# Sheet4.net
KiCad netlist of a schematic drawn in Altium Designer
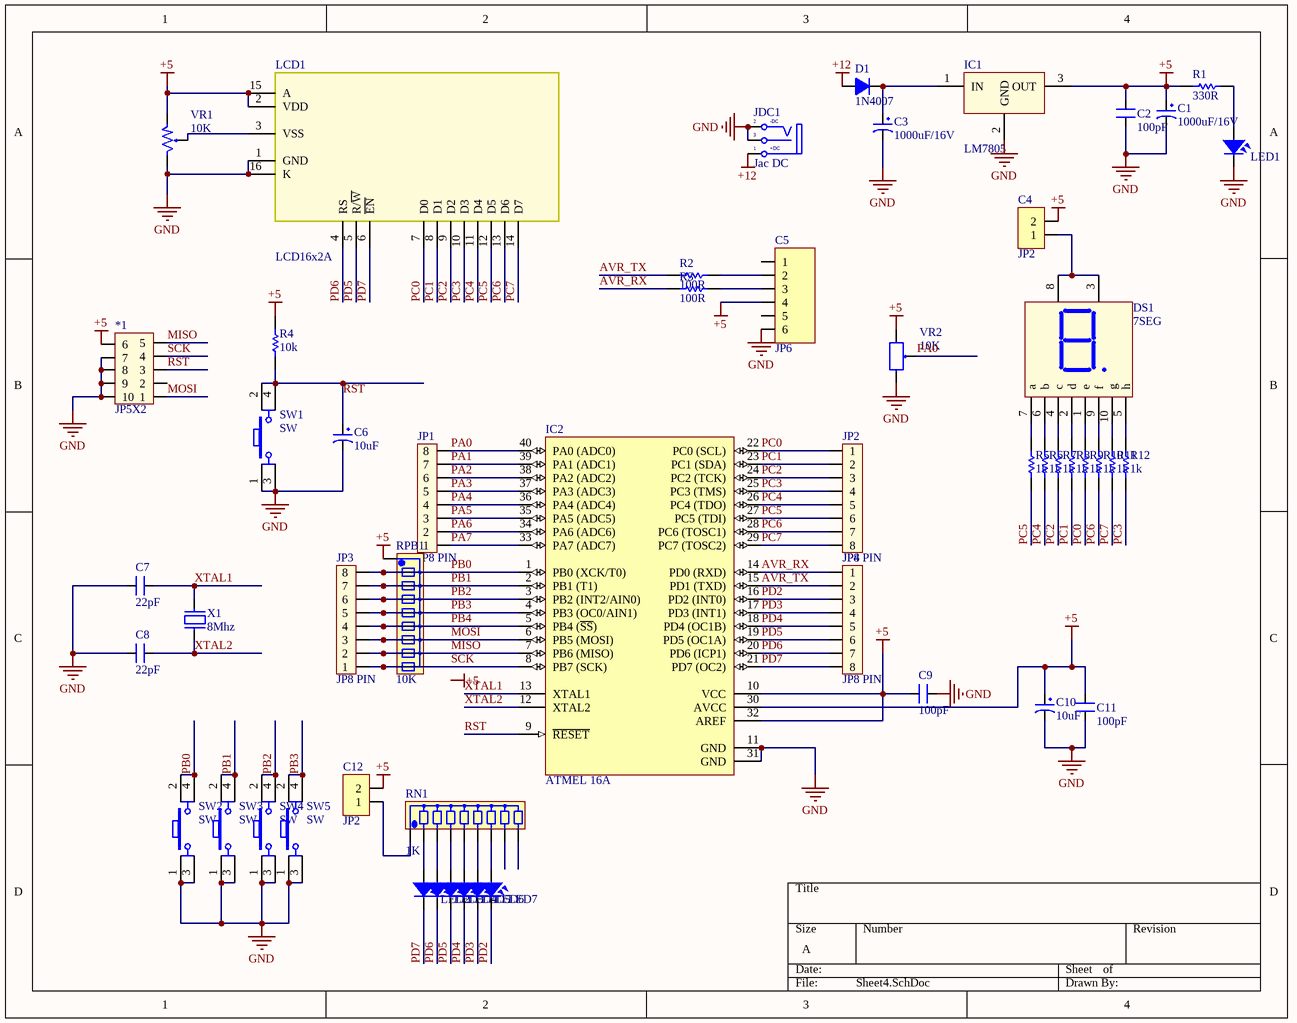
[diagram p0: Sheet4.SchDoc]

(export (version "E")
  (design (tool "Eeschema 10.0.6"))
  (components
    (comp (ref "*1") (value "JP5X2") (footprint "JP5X2") (libsource (lib "syhaunguyen") (part "JP5X2")))
    (comp (ref "C1")
      (value "1000uF/16V")
      (footprint "CP1.5/3.4")
      (description "Cap 1000uF/16V - 220uF/50V")
      (libsource (lib "syhaunguyen") (part "CP4"))
    )
    (comp (ref "C2")
      (value "100pF")
      (footprint "CN1")
      (description "Cap np  1pF - 472pF")
      (libsource (lib "syhaunguyen") (part "CN1"))
    )
    (comp (ref "C3")
      (value "1000uF/16V")
      (footprint "CP1.5/3.4")
      (description "Cap 1000uF/16V - 220uF/50V")
      (libsource (lib "syhaunguyen") (part "CP4"))
    )
    (comp (ref "C4")
      (value "JP2")
      (footprint "JP2-D1T")
      (description "WR-PHD 2.54 mm Angled Socket Header")
      (fields
        (field (name "MANUFACTURER") "Würth Elektronik eiSos GmbH")
        (field (name "PARTNO") "613002143121")
        (field (name "CREATED BY") "Karrer Zheng")
      )
      (libsource (lib "TechMT.VN_Lib_Project v2") (part "JP2"))
    )
    (comp (ref "C5")
      (value "JP6")
      (footprint "JP6-D1T")
      (description "WR-PHD 2.54 mm Angled Socket Header")
      (fields
        (field (name "MANUFACTURER") "Würth Elektronik eiSos GmbH")
        (field (name "PARTNO") "613006143121")
        (field (name "CREATED BY") "Karrer Zheng")
      )
      (libsource (lib "LIBRARY") (part "JP6"))
    )
    (comp (ref "C6")
      (value "10uF")
      (footprint "CP1/2")
      (description "Cap P  0,1uF < 22uF , 16 - 50V")
      (libsource (lib "syhaunguyen") (part "CP1"))
    )
    (comp (ref "C7")
      (value "22pF")
      (footprint "CN1")
      (description "Cap np  1pF - 472pF")
      (libsource (lib "syhaunguyen") (part "CN1"))
    )
    (comp (ref "C8")
      (value "22pF")
      (footprint "CN1")
      (description "Cap np  1pF - 472pF")
      (libsource (lib "syhaunguyen") (part "CN1"))
    )
    (comp (ref "C9")
      (value "100pF")
      (footprint "CN1")
      (description "Cap np  1pF - 472pF")
      (libsource (lib "syhaunguyen") (part "CN1"))
    )
    (comp (ref "C10")
      (value "10uF")
      (footprint "CP1/2")
      (description "Cap P  0,1uF < 22uF , 16 - 50V")
      (libsource (lib "syhaunguyen") (part "CP1"))
    )
    (comp (ref "C11")
      (value "100pF")
      (footprint "CN1")
      (description "Cap np  1pF - 472pF")
      (libsource (lib "syhaunguyen") (part "CN1"))
    )
    (comp (ref "C12")
      (value "JP2")
      (footprint "JP2-D1T")
      (description "WR-PHD 2.54 mm Angled Socket Header")
      (fields
        (field (name "MANUFACTURER") "Würth Elektronik eiSos GmbH")
        (field (name "PARTNO") "613002143121")
        (field (name "CREATED BY") "Karrer Zheng")
      )
      (libsource (lib "TechMT.VN_Lib_Project v2") (part "JP2"))
    )
    (comp (ref "D1")
      (value "1N4007")
      (footprint "D1A")
      (description "Diode 1A")
      (libsource (lib "syhaunguyen") (part "D1A"))
    )
    (comp (ref "DS1")
      (value "7SEG")
      (footprint "LED7SEG-1-0.56")
      (description "14.2 mm General Purpose Blue 7-Segment Display: CC, RH DP, Gray Surface")
      (fields (field (name "PUBLISHER") "Altium Limited"))
      (libsource (lib "TechMT.VN_Lib_Project v2") (part "LED7SEG-1"))
    )
    (comp (ref "IC1")
      (value "LM7805")
      (footprint "QTO-220")
      (description "On ap +, from + 5 to + 24VDC")
      (libsource (lib "syhaunguyen") (part "LM78xx"))
    )
    (comp (ref "IC2")
      (value "ATMEL 16A")
      (footprint "DIP40/W0.6")
      (description "8-Bit AVR Microcontroller with 16K Bytes of In-System Programmable Flash Memory")
      (libsource (lib "LIBRARY") (part "ATmega16A-PU"))
    )
    (comp (ref "JDC1")
      (value "Jac DC")
      (footprint "DC-IN")
      (description "Jac DC input")
      (libsource (lib "syhaunguyen") (part "DCIN"))
    )
    (comp (ref "JP1") (value "JP8 PIN") (footprint "JP8") (libsource (lib "") (part "JP8_1")))
    (comp (ref "JP2") (value "JP8 PIN") (footprint "JP8") (libsource (lib "syhaunguyen") (part "JP8")))
    (comp (ref "JP3") (value "JP8 PIN") (footprint "JP8") (libsource (lib "") (part "JP8_1")))
    (comp (ref "JP4") (value "JP8 PIN") (footprint "JP8") (libsource (lib "syhaunguyen") (part "JP8")))
    (comp (ref "LCD1")
      (value "LCD16x2A")
      (footprint "LCD16X2")
      (description "LCD dipslay 16 char, 2 line")
      (libsource (lib "syhaunguyen") (part "LCD16x2"))
    )
    (comp (ref "LED1")
      (value "LED")
      (footprint "LED-5-RED")
      (description "LED Single colour Green and Red")
      (libsource (lib "syhaunguyen") (part "LED"))
    )
    (comp (ref "LED2")
      (value "LED")
      (footprint "LED-3")
      (description "LED Single colour Green and Red")
      (libsource (lib "syhaunguyen") (part "LED"))
    )
    (comp (ref "LED3")
      (value "LED")
      (footprint "LED-3")
      (description "LED Single colour Green and Red")
      (libsource (lib "syhaunguyen") (part "LED"))
    )
    (comp (ref "LED4")
      (value "LED")
      (footprint "LED-3")
      (description "LED Single colour Green and Red")
      (libsource (lib "syhaunguyen") (part "LED"))
    )
    (comp (ref "LED5")
      (value "LED")
      (footprint "LED-3")
      (description "LED Single colour Green and Red")
      (libsource (lib "syhaunguyen") (part "LED"))
    )
    (comp (ref "LED6")
      (value "LED")
      (footprint "LED-3")
      (description "LED Single colour Green and Red")
      (libsource (lib "syhaunguyen") (part "LED"))
    )
    (comp (ref "LED7")
      (value "LED")
      (footprint "LED-3")
      (description "LED Single colour Green and Red")
      (libsource (lib "syhaunguyen") (part "LED"))
    )
    (comp (ref "R1")
      (value "330R")
      (footprint "R1/4W")
      (description "Resistor")
      (fields
        (field (name "MANUFACTURER") "Generic Components")
        (field (name "Comment") "Res1")
        (field (name "PUBLISHER") "Altium Hobart Technology Centre")
      )
      (libsource (lib "syhaunguyen") (part "Res1_1"))
    )
    (comp (ref "R2")
      (value "100R")
      (footprint "R1/4W")
      (description "Resistor")
      (fields
        (field (name "MANUFACTURER") "Generic Components")
        (field (name "Comment") "Res1")
        (field (name "PUBLISHER") "Altium Hobart Technology Centre")
      )
      (libsource (lib "syhaunguyen") (part "Res1_1"))
    )
    (comp (ref "R3")
      (value "100R")
      (footprint "R1/4W")
      (description "Resistor")
      (fields
        (field (name "MANUFACTURER") "Generic Components")
        (field (name "Comment") "Res1")
        (field (name "PUBLISHER") "Altium Hobart Technology Centre")
      )
      (libsource (lib "syhaunguyen") (part "Res1_1"))
    )
    (comp (ref "R4")
      (value "10k")
      (footprint "R1/4W")
      (description "Resistor")
      (fields
        (field (name "MANUFACTURER") "Generic Components")
        (field (name "Comment") "Res1")
        (field (name "PUBLISHER") "Altium Hobart Technology Centre")
      )
      (libsource (lib "syhaunguyen") (part "Res1_1"))
    )
    (comp (ref "R5")
      (value "1k")
      (footprint "R1/4W")
      (description "Resistor")
      (fields
        (field (name "MANUFACTURER") "Generic Components")
        (field (name "Comment") "Res1")
        (field (name "PUBLISHER") "Altium Hobart Technology Centre")
      )
      (libsource (lib "syhaunguyen") (part "Res1_1"))
    )
    (comp (ref "R6")
      (value "1k")
      (footprint "R1/4W")
      (description "Resistor")
      (fields
        (field (name "MANUFACTURER") "Generic Components")
        (field (name "Comment") "Res1")
        (field (name "PUBLISHER") "Altium Hobart Technology Centre")
      )
      (libsource (lib "syhaunguyen") (part "Res1_1"))
    )
    (comp (ref "R7")
      (value "1k")
      (footprint "R1/4W")
      (description "Resistor")
      (fields
        (field (name "MANUFACTURER") "Generic Components")
        (field (name "Comment") "Res1")
        (field (name "PUBLISHER") "Altium Hobart Technology Centre")
      )
      (libsource (lib "syhaunguyen") (part "Res1_1"))
    )
    (comp (ref "R8")
      (value "1k")
      (footprint "R1/4W")
      (description "Resistor")
      (fields
        (field (name "MANUFACTURER") "Generic Components")
        (field (name "Comment") "Res1")
        (field (name "PUBLISHER") "Altium Hobart Technology Centre")
      )
      (libsource (lib "syhaunguyen") (part "Res1_1"))
    )
    (comp (ref "R9")
      (value "1k")
      (footprint "R1/4W")
      (description "Resistor")
      (fields
        (field (name "MANUFACTURER") "Generic Components")
        (field (name "Comment") "Res1")
        (field (name "PUBLISHER") "Altium Hobart Technology Centre")
      )
      (libsource (lib "syhaunguyen") (part "Res1_1"))
    )
    (comp (ref "R10")
      (value "1k")
      (footprint "R1/4W")
      (description "Resistor")
      (fields
        (field (name "MANUFACTURER") "Generic Components")
        (field (name "Comment") "Res1")
        (field (name "PUBLISHER") "Altium Hobart Technology Centre")
      )
      (libsource (lib "syhaunguyen") (part "Res1_1"))
    )
    (comp (ref "R11")
      (value "1k")
      (footprint "R1/4W")
      (description "Resistor")
      (fields
        (field (name "MANUFACTURER") "Generic Components")
        (field (name "Comment") "Res1")
        (field (name "PUBLISHER") "Altium Hobart Technology Centre")
      )
      (libsource (lib "syhaunguyen") (part "Res1_1"))
    )
    (comp (ref "R12")
      (value "1k")
      (footprint "R1/4W")
      (description "Resistor")
      (fields
        (field (name "MANUFACTURER") "Generic Components")
        (field (name "Comment") "Res1")
        (field (name "PUBLISHER") "Altium Hobart Technology Centre")
      )
      (libsource (lib "syhaunguyen") (part "Res1_1"))
    )
    (comp (ref "RN1")
      (value "1K")
      (footprint "RN8")
      (description "Resistor 8 (Thanh)")
      (libsource (lib "syhaunguyen") (part "RN8"))
    )
    (comp (ref "RPB1")
      (value "10K")
      (footprint "RN8")
      (description "Resistor 8 (Thanh)")
      (libsource (lib "LIBRARY") (part "RN8"))
    )
    (comp (ref "SW1")
      (value "SW")
      (footprint "SW4")
      (description "Switch button 4 pin")
      (libsource (lib "syhaunguyen") (part "SW4"))
    )
    (comp (ref "SW2")
      (value "SW")
      (footprint "SW4")
      (description "Switch button 4 pin")
      (libsource (lib "syhaunguyen") (part "SW4"))
    )
    (comp (ref "SW3")
      (value "SW")
      (footprint "SW4")
      (description "Switch button 4 pin")
      (libsource (lib "syhaunguyen") (part "SW4"))
    )
    (comp (ref "SW4")
      (value "SW")
      (footprint "SW4")
      (description "Switch button 4 pin")
      (libsource (lib "syhaunguyen") (part "SW4"))
    )
    (comp (ref "SW5")
      (value "SW")
      (footprint "SW4")
      (description "Switch button 4 pin")
      (libsource (lib "syhaunguyen") (part "SW4"))
    )
    (comp (ref "VR1")
      (value "10K")
      (footprint "VR")
      (description "Var Resistor")
      (libsource (lib "syhaunguyen") (part "VR1"))
    )
    (comp (ref "VR2")
      (value "10K")
      (footprint "VR1")
      (description "Var Resistor")
      (libsource (lib "syhaunguyen") (part "VR"))
    )
    (comp (ref "X1")
      (value "8Mhz")
      (footprint "XT2")
      (description "Crystal For all Crystal 2pin.")
      (libsource (lib "syhaunguyen") (part "XT2"))
    )
  )
  (nets
    (net (code "1") (name "+5") (class "Default")
      (node (ref "*1") (pin "6") (pinfunction "6_6") (pintype "passive"))
      (node (ref "C1") (pin "1") (pinfunction "1_1") (pintype "passive"))
      (node (ref "C10") (pin "1") (pinfunction "1_1") (pintype "passive"))
      (node (ref "C11") (pin "2") (pinfunction "2_2") (pintype "passive"))
      (node (ref "C12") (pin "2") (pinfunction "2_2") (pintype "passive"))
      (node (ref "C2") (pin "1") (pinfunction "1_1") (pintype "passive"))
      (node (ref "C4") (pin "2") (pinfunction "2_2") (pintype "passive"))
      (node (ref "C5") (pin "4") (pinfunction "4_4") (pintype "passive"))
      (node (ref "C9") (pin "1") (pinfunction "1_1") (pintype "passive"))
      (node (ref "IC1") (pin "3") (pinfunction "OUT_3") (pintype "passive"))
      (node (ref "IC2") (pin "10") (pinfunction "VCC_10") (pintype "power_in"))
      (node (ref "IC2") (pin "30") (pinfunction "AVCC_30") (pintype "power_in"))
      (node (ref "IC2") (pin "32") (pinfunction "AREF_32") (pintype "power_in"))
      (node (ref "LCD1") (pin "15") (pinfunction "A_15") (pintype "passive"))
      (node (ref "LCD1") (pin "2") (pinfunction "VDD_2") (pintype "passive"))
      (node (ref "R1") (pin "2") (pinfunction "2_2") (pintype "passive"))
      (node (ref "R4") (pin "1") (pinfunction "1_1") (pintype "passive"))
      (node (ref "RPB1") (pin "1") (pinfunction "1_1") (pintype "passive"))
      (node (ref "VR1") (pin "1") (pinfunction "1_1") (pintype "passive"))
      (node (ref "VR2") (pin "1") (pinfunction "1_1") (pintype "passive"))
    )
    (net (code "2") (name "+12") (class "Default")
      (node (ref "D1") (pin "1") (pinfunction "A_1") (pintype "passive"))
      (node (ref "JDC1") (pin "1") (pinfunction "T_1") (pintype "passive"))
    )
    (net (code "3") (name "/AVR_RX") (class "Default")
      (node (ref "IC2") (pin "14") (pinfunction "PD0_(RXD)_14") (pintype "bidirectional"))
      (node (ref "JP4") (pin "1") (pinfunction "1_1") (pintype "passive"))
      (node (ref "R3") (pin "2") (pinfunction "2_2") (pintype "passive"))
    )
    (net (code "4") (name "/AVR_TX") (class "Default")
      (node (ref "IC2") (pin "15") (pinfunction "PD1_(TXD)_15") (pintype "bidirectional"))
      (node (ref "JP4") (pin "2") (pinfunction "2_2") (pintype "passive"))
      (node (ref "R2") (pin "2") (pinfunction "2_2") (pintype "passive"))
    )
    (net (code "5") (name "/MISO") (class "Default")
      (node (ref "*1") (pin "5") (pinfunction "5_5") (pintype "passive"))
      (node (ref "IC2") (pin "7") (pinfunction "PB6_(MISO)_7") (pintype "bidirectional"))
      (node (ref "JP3") (pin "2") (pinfunction "2_2") (pintype "passive"))
      (node (ref "RPB1") (pin "8") (pinfunction "8_8") (pintype "passive"))
    )
    (net (code "6") (name "/MOSI") (class "Default")
      (node (ref "*1") (pin "1") (pinfunction "1_1") (pintype "passive"))
      (node (ref "IC2") (pin "6") (pinfunction "PB5_(MOSI)_6") (pintype "bidirectional"))
      (node (ref "JP3") (pin "3") (pinfunction "3_3") (pintype "passive"))
      (node (ref "RPB1") (pin "7") (pinfunction "7_7") (pintype "passive"))
    )
    (net (code "7") (name "/PA0") (class "Default")
      (node (ref "IC2") (pin "40") (pinfunction "PA0_(ADC0)_40") (pintype "bidirectional"))
      (node (ref "JP1") (pin "8") (pinfunction "8_8") (pintype "passive"))
      (node (ref "VR2") (pin "2") (pinfunction "2_2") (pintype "passive"))
    )
    (net (code "8") (name "/PA1") (class "Default")
      (node (ref "IC2") (pin "39") (pinfunction "PA1_(ADC1)_39") (pintype "bidirectional"))
      (node (ref "JP1") (pin "7") (pinfunction "7_7") (pintype "passive"))
    )
    (net (code "9") (name "/PA2") (class "Default")
      (node (ref "IC2") (pin "38") (pinfunction "PA2_(ADC2)_38") (pintype "bidirectional"))
      (node (ref "JP1") (pin "6") (pinfunction "6_6") (pintype "passive"))
    )
    (net (code "10") (name "/PA3") (class "Default")
      (node (ref "IC2") (pin "37") (pinfunction "PA3_(ADC3)_37") (pintype "bidirectional"))
      (node (ref "JP1") (pin "5") (pinfunction "5_5") (pintype "passive"))
    )
    (net (code "11") (name "/PA4") (class "Default")
      (node (ref "IC2") (pin "36") (pinfunction "PA4_(ADC4)_36") (pintype "bidirectional"))
      (node (ref "JP1") (pin "4") (pinfunction "4_4") (pintype "passive"))
    )
    (net (code "12") (name "/PA5") (class "Default")
      (node (ref "IC2") (pin "35") (pinfunction "PA5_(ADC5)_35") (pintype "bidirectional"))
      (node (ref "JP1") (pin "3") (pinfunction "3_3") (pintype "passive"))
    )
    (net (code "13") (name "/PA6") (class "Default")
      (node (ref "IC2") (pin "34") (pinfunction "PA6_(ADC6)_34") (pintype "bidirectional"))
      (node (ref "JP1") (pin "2") (pinfunction "2_2") (pintype "passive"))
    )
    (net (code "14") (name "/PA7") (class "Default")
      (node (ref "IC2") (pin "33") (pinfunction "PA7_(ADC7)_33") (pintype "bidirectional"))
      (node (ref "JP1") (pin "1") (pinfunction "1_1") (pintype "passive"))
    )
    (net (code "15") (name "/PB0") (class "Default")
      (node (ref "IC2") (pin "1") (pinfunction "PB0_(XCK/T0)_1") (pintype "bidirectional"))
      (node (ref "JP3") (pin "8") (pinfunction "8_8") (pintype "passive"))
      (node (ref "RPB1") (pin "2") (pinfunction "2_2") (pintype "passive"))
      (node (ref "SW2") (pin "2") (pintype "passive"))
      (node (ref "SW2") (pin "4") (pintype "passive"))
    )
    (net (code "16") (name "/PB1") (class "Default")
      (node (ref "IC2") (pin "2") (pinfunction "PB1_(T1)_2") (pintype "bidirectional"))
      (node (ref "JP3") (pin "7") (pinfunction "7_7") (pintype "passive"))
      (node (ref "RPB1") (pin "3") (pinfunction "3_3") (pintype "passive"))
      (node (ref "SW3") (pin "2") (pintype "passive"))
      (node (ref "SW3") (pin "4") (pintype "passive"))
    )
    (net (code "17") (name "/PB2") (class "Default")
      (node (ref "IC2") (pin "3") (pinfunction "PB2_(INT2/AIN0)_3") (pintype "bidirectional"))
      (node (ref "JP3") (pin "6") (pinfunction "6_6") (pintype "passive"))
      (node (ref "RPB1") (pin "4") (pinfunction "4_4") (pintype "passive"))
      (node (ref "SW4") (pin "2") (pintype "passive"))
      (node (ref "SW4") (pin "4") (pintype "passive"))
    )
    (net (code "18") (name "/PB3") (class "Default")
      (node (ref "IC2") (pin "4") (pinfunction "PB3_(OC0/AIN1)_4") (pintype "bidirectional"))
      (node (ref "JP3") (pin "5") (pinfunction "5_5") (pintype "passive"))
      (node (ref "RPB1") (pin "5") (pinfunction "5_5") (pintype "passive"))
      (node (ref "SW5") (pin "2") (pintype "passive"))
      (node (ref "SW5") (pin "4") (pintype "passive"))
    )
    (net (code "19") (name "/PB4") (class "Default")
      (node (ref "IC2") (pin "5") (pinfunction "PB4_(~{SS})_5") (pintype "bidirectional"))
      (node (ref "JP3") (pin "4") (pinfunction "4_4") (pintype "passive"))
      (node (ref "RPB1") (pin "6") (pinfunction "6_6") (pintype "passive"))
    )
    (net (code "20") (name "/PC0") (class "Default")
      (node (ref "IC2") (pin "22") (pinfunction "PC0_(SCL)_22") (pintype "bidirectional"))
      (node (ref "JP2") (pin "1") (pinfunction "1_1") (pintype "passive"))
      (node (ref "LCD1") (pin "7") (pinfunction "D0_7") (pintype "passive"))
      (node (ref "R9") (pin "2") (pinfunction "2_2") (pintype "passive"))
    )
    (net (code "21") (name "/PC1") (class "Default")
      (node (ref "IC2") (pin "23") (pinfunction "PC1_(SDA)_23") (pintype "bidirectional"))
      (node (ref "JP2") (pin "2") (pinfunction "2_2") (pintype "passive"))
      (node (ref "LCD1") (pin "8") (pinfunction "D1_8") (pintype "passive"))
      (node (ref "R8") (pin "2") (pinfunction "2_2") (pintype "passive"))
    )
    (net (code "22") (name "/PC2") (class "Default")
      (node (ref "IC2") (pin "24") (pinfunction "PC2_(TCK)_24") (pintype "bidirectional"))
      (node (ref "JP2") (pin "3") (pinfunction "3_3") (pintype "passive"))
      (node (ref "LCD1") (pin "9") (pinfunction "D2_9") (pintype "passive"))
      (node (ref "R7") (pin "2") (pinfunction "2_2") (pintype "passive"))
    )
    (net (code "23") (name "/PC3") (class "Default")
      (node (ref "IC2") (pin "25") (pinfunction "PC3_(TMS)_25") (pintype "bidirectional"))
      (node (ref "JP2") (pin "4") (pinfunction "4_4") (pintype "passive"))
      (node (ref "LCD1") (pin "10") (pinfunction "D3_10") (pintype "passive"))
      (node (ref "R12") (pin "2") (pinfunction "2_2") (pintype "passive"))
    )
    (net (code "24") (name "/PC4") (class "Default")
      (node (ref "IC2") (pin "26") (pinfunction "PC4_(TDO)_26") (pintype "bidirectional"))
      (node (ref "JP2") (pin "5") (pinfunction "5_5") (pintype "passive"))
      (node (ref "LCD1") (pin "11") (pinfunction "D4_11") (pintype "passive"))
      (node (ref "R6") (pin "2") (pinfunction "2_2") (pintype "passive"))
    )
    (net (code "25") (name "/PC5") (class "Default")
      (node (ref "IC2") (pin "27") (pinfunction "PC5_(TDI)_27") (pintype "bidirectional"))
      (node (ref "JP2") (pin "6") (pinfunction "6_6") (pintype "passive"))
      (node (ref "LCD1") (pin "12") (pinfunction "D5_12") (pintype "passive"))
      (node (ref "R5") (pin "2") (pinfunction "2_2") (pintype "passive"))
    )
    (net (code "26") (name "/PC6") (class "Default")
      (node (ref "IC2") (pin "28") (pinfunction "PC6_(TOSC1)_28") (pintype "bidirectional"))
      (node (ref "JP2") (pin "7") (pinfunction "7_7") (pintype "passive"))
      (node (ref "LCD1") (pin "13") (pinfunction "D6_13") (pintype "passive"))
      (node (ref "R10") (pin "2") (pinfunction "2_2") (pintype "passive"))
    )
    (net (code "27") (name "/PC7") (class "Default")
      (node (ref "IC2") (pin "29") (pinfunction "PC7_(TOSC2)_29") (pintype "bidirectional"))
      (node (ref "JP2") (pin "8") (pinfunction "8_8") (pintype "passive"))
      (node (ref "LCD1") (pin "14") (pinfunction "D7_14") (pintype "passive"))
      (node (ref "R11") (pin "2") (pinfunction "2_2") (pintype "passive"))
    )
    (net (code "28") (name "/PD2") (class "Default")
      (node (ref "IC2") (pin "16") (pinfunction "PD2_(INT0)_16") (pintype "bidirectional"))
      (node (ref "JP4") (pin "3") (pinfunction "3_3") (pintype "passive"))
      (node (ref "LED7") (pin "2") (pinfunction "2_2") (pintype "passive"))
    )
    (net (code "29") (name "/PD3") (class "Default")
      (node (ref "IC2") (pin "17") (pinfunction "PD3_(INT1)_17") (pintype "bidirectional"))
      (node (ref "JP4") (pin "4") (pinfunction "4_4") (pintype "passive"))
      (node (ref "LED6") (pin "2") (pinfunction "2_2") (pintype "passive"))
    )
    (net (code "30") (name "/PD4") (class "Default")
      (node (ref "IC2") (pin "18") (pinfunction "PD4_(OC1B)_18") (pintype "bidirectional"))
      (node (ref "JP4") (pin "5") (pinfunction "5_5") (pintype "passive"))
      (node (ref "LED5") (pin "2") (pinfunction "2_2") (pintype "passive"))
    )
    (net (code "31") (name "/PD5") (class "Default")
      (node (ref "IC2") (pin "19") (pinfunction "PD5_(OC1A)_19") (pintype "bidirectional"))
      (node (ref "JP4") (pin "6") (pinfunction "6_6") (pintype "passive"))
      (node (ref "LCD1") (pin "5") (pinfunction "R/~{W}_5") (pintype "passive"))
      (node (ref "LED4") (pin "2") (pinfunction "2_2") (pintype "passive"))
    )
    (net (code "32") (name "/PD6") (class "Default")
      (node (ref "IC2") (pin "20") (pinfunction "PD6_(ICP1)_20") (pintype "bidirectional"))
      (node (ref "JP4") (pin "7") (pinfunction "7_7") (pintype "passive"))
      (node (ref "LCD1") (pin "4") (pinfunction "RS_4") (pintype "passive"))
      (node (ref "LED3") (pin "2") (pinfunction "2_2") (pintype "passive"))
    )
    (net (code "33") (name "/PD7") (class "Default")
      (node (ref "IC2") (pin "21") (pinfunction "PD7_(OC2)_21") (pintype "bidirectional"))
      (node (ref "JP4") (pin "8") (pinfunction "8_8") (pintype "passive"))
      (node (ref "LCD1") (pin "6") (pinfunction "~{EN}_6") (pintype "passive"))
      (node (ref "LED2") (pin "2") (pinfunction "2_2") (pintype "passive"))
    )
    (net (code "34") (name "/RST") (class "Default")
      (node (ref "*1") (pin "3") (pinfunction "3_3") (pintype "passive"))
      (node (ref "C6") (pin "1") (pinfunction "1_1") (pintype "passive"))
      (node (ref "IC2") (pin "9") (pinfunction "~{RESET}_9") (pintype "input"))
      (node (ref "R4") (pin "2") (pinfunction "2_2") (pintype "passive"))
      (node (ref "SW1") (pin "2") (pintype "passive"))
      (node (ref "SW1") (pin "4") (pintype "passive"))
    )
    (net (code "35") (name "/SCK") (class "Default")
      (node (ref "*1") (pin "4") (pinfunction "4_4") (pintype "passive"))
      (node (ref "IC2") (pin "8") (pinfunction "PB7_(SCK)_8") (pintype "bidirectional"))
      (node (ref "JP3") (pin "1") (pinfunction "1_1") (pintype "passive"))
      (node (ref "RPB1") (pin "9") (pinfunction "9_9") (pintype "passive"))
    )
    (net (code "36") (name "/XTAL1") (class "Default")
      (node (ref "C7") (pin "2") (pinfunction "2_2") (pintype "passive"))
      (node (ref "IC2") (pin "13") (pinfunction "XTAL1_13") (pintype "passive"))
      (node (ref "X1") (pin "2") (pinfunction "2_2") (pintype "passive"))
    )
    (net (code "37") (name "/XTAL2") (class "Default")
      (node (ref "C8") (pin "2") (pinfunction "2_2") (pintype "passive"))
      (node (ref "IC2") (pin "12") (pinfunction "XTAL2_12") (pintype "passive"))
      (node (ref "X1") (pin "1") (pinfunction "1_1") (pintype "passive"))
    )
    (net (code "38") (name "GND") (class "Default")
      (node (ref "*1") (pin "10") (pinfunction "10_10") (pintype "passive"))
      (node (ref "*1") (pin "7") (pinfunction "7_7") (pintype "passive"))
      (node (ref "*1") (pin "8") (pinfunction "8_8") (pintype "passive"))
      (node (ref "*1") (pin "9") (pinfunction "9_9") (pintype "passive"))
      (node (ref "C1") (pin "2") (pinfunction "2_2") (pintype "passive"))
      (node (ref "C10") (pin "2") (pinfunction "2_2") (pintype "passive"))
      (node (ref "C11") (pin "1") (pinfunction "1_1") (pintype "passive"))
      (node (ref "C2") (pin "2") (pinfunction "2_2") (pintype "passive"))
      (node (ref "C3") (pin "2") (pinfunction "2_2") (pintype "passive"))
      (node (ref "C5") (pin "6") (pinfunction "6_6") (pintype "passive"))
      (node (ref "C6") (pin "2") (pinfunction "2_2") (pintype "passive"))
      (node (ref "C7") (pin "1") (pinfunction "1_1") (pintype "passive"))
      (node (ref "C8") (pin "1") (pinfunction "1_1") (pintype "passive"))
      (node (ref "C9") (pin "2") (pinfunction "2_2") (pintype "passive"))
      (node (ref "IC1") (pin "2") (pinfunction "GND_2") (pintype "passive"))
      (node (ref "IC2") (pin "11") (pinfunction "GND_11") (pintype "power_in"))
      (node (ref "IC2") (pin "31") (pinfunction "GND_31") (pintype "power_in"))
      (node (ref "JDC1") (pin "2") (pinfunction "TN_2") (pintype "passive"))
      (node (ref "JDC1") (pin "3") (pinfunction "S_3") (pintype "power_in"))
      (node (ref "LCD1") (pin "1") (pinfunction "GND_1") (pintype "passive"))
      (node (ref "LCD1") (pin "16") (pinfunction "K_16") (pintype "passive"))
      (node (ref "LED1") (pin "2") (pinfunction "2_2") (pintype "passive"))
      (node (ref "SW1") (pin "1") (pintype "passive"))
      (node (ref "SW1") (pin "3") (pintype "passive"))
      (node (ref "SW2") (pin "1") (pintype "passive"))
      (node (ref "SW2") (pin "3") (pintype "passive"))
      (node (ref "SW3") (pin "1") (pintype "passive"))
      (node (ref "SW3") (pin "3") (pintype "passive"))
      (node (ref "SW4") (pin "1") (pintype "passive"))
      (node (ref "SW4") (pin "3") (pintype "passive"))
      (node (ref "SW5") (pin "1") (pintype "passive"))
      (node (ref "SW5") (pin "3") (pintype "passive"))
      (node (ref "VR1") (pin "3") (pinfunction "3_3") (pintype "passive"))
      (node (ref "VR2") (pin "3") (pinfunction "3_3") (pintype "passive"))
    )
    (net (code "39") (name "Net-(C4-Pad1)") (class "Default")
      (node (ref "C4") (pin "1") (pinfunction "1_1") (pintype "passive"))
      (node (ref "DS1") (pin "3") (pinfunction "Vcc_3") (pintype "passive"))
      (node (ref "DS1") (pin "8") (pinfunction "Vcc_8") (pintype "passive"))
    )
    (net (code "40") (name "Net-(C5-Pad2)") (class "Default")
      (node (ref "C5") (pin "2") (pinfunction "2_2") (pintype "passive"))
      (node (ref "R2") (pin "1") (pinfunction "1_1") (pintype "passive"))
    )
    (net (code "41") (name "Net-(C5-Pad3)") (class "Default")
      (node (ref "C5") (pin "3") (pinfunction "3_3") (pintype "passive"))
      (node (ref "R3") (pin "1") (pinfunction "1_1") (pintype "passive"))
    )
    (net (code "42") (name "Net-(C12-Pad1)") (class "Default")
      (node (ref "C12") (pin "1") (pinfunction "1_1") (pintype "passive"))
      (node (ref "RN1") (pin "1") (pinfunction "1_1") (pintype "passive"))
    )
    (net (code "43") (name "Net-(D1-K)") (class "Default")
      (node (ref "C3") (pin "1") (pinfunction "1_1") (pintype "passive"))
      (node (ref "D1") (pin "2") (pinfunction "K_2") (pintype "passive"))
      (node (ref "IC1") (pin "1") (pinfunction "IN_1") (pintype "passive"))
    )
    (net (code "44") (name "Net-(DS1-a)") (class "Default")
      (node (ref "DS1") (pin "7") (pinfunction "a_7") (pintype "passive"))
      (node (ref "R5") (pin "1") (pinfunction "1_1") (pintype "passive"))
    )
    (net (code "45") (name "Net-(DS1-b)") (class "Default")
      (node (ref "DS1") (pin "6") (pinfunction "b_6") (pintype "passive"))
      (node (ref "R6") (pin "1") (pinfunction "1_1") (pintype "passive"))
    )
    (net (code "46") (name "Net-(DS1-c)") (class "Default")
      (node (ref "DS1") (pin "4") (pinfunction "c_4") (pintype "passive"))
      (node (ref "R7") (pin "1") (pinfunction "1_1") (pintype "passive"))
    )
    (net (code "47") (name "Net-(DS1-d)") (class "Default")
      (node (ref "DS1") (pin "2") (pinfunction "d_2") (pintype "passive"))
      (node (ref "R8") (pin "1") (pinfunction "1_1") (pintype "passive"))
    )
    (net (code "48") (name "Net-(DS1-e)") (class "Default")
      (node (ref "DS1") (pin "1") (pinfunction "e_1") (pintype "passive"))
      (node (ref "R9") (pin "1") (pinfunction "1_1") (pintype "passive"))
    )
    (net (code "49") (name "Net-(DS1-f)") (class "Default")
      (node (ref "DS1") (pin "9") (pinfunction "f_9") (pintype "passive"))
      (node (ref "R10") (pin "1") (pinfunction "1_1") (pintype "passive"))
    )
    (net (code "50") (name "Net-(DS1-g)") (class "Default")
      (node (ref "DS1") (pin "10") (pinfunction "g_10") (pintype "passive"))
      (node (ref "R11") (pin "1") (pinfunction "1_1") (pintype "passive"))
    )
    (net (code "51") (name "Net-(DS1-h)") (class "Default")
      (node (ref "DS1") (pin "5") (pinfunction "h_5") (pintype "passive"))
      (node (ref "R12") (pin "1") (pinfunction "1_1") (pintype "passive"))
    )
    (net (code "52") (name "Net-(LCD1-VSS)") (class "Default")
      (node (ref "LCD1") (pin "3") (pinfunction "VSS_3") (pintype "passive"))
      (node (ref "VR1") (pin "2") (pinfunction "2_2") (pintype "passive"))
    )
    (net (code "53") (name "Net-(LED1-Pad1)") (class "Default")
      (node (ref "LED1") (pin "1") (pinfunction "1_1") (pintype "passive"))
      (node (ref "R1") (pin "1") (pinfunction "1_1") (pintype "passive"))
    )
    (net (code "54") (name "Net-(LED2-Pad1)") (class "Default")
      (node (ref "LED2") (pin "1") (pinfunction "1_1") (pintype "passive"))
      (node (ref "RN1") (pin "2") (pinfunction "2_2") (pintype "passive"))
    )
    (net (code "55") (name "Net-(LED3-Pad1)") (class "Default")
      (node (ref "LED3") (pin "1") (pinfunction "1_1") (pintype "passive"))
      (node (ref "RN1") (pin "3") (pinfunction "3_3") (pintype "passive"))
    )
    (net (code "56") (name "Net-(LED4-Pad1)") (class "Default")
      (node (ref "LED4") (pin "1") (pinfunction "1_1") (pintype "passive"))
      (node (ref "RN1") (pin "4") (pinfunction "4_4") (pintype "passive"))
    )
    (net (code "57") (name "Net-(LED5-Pad1)") (class "Default")
      (node (ref "LED5") (pin "1") (pinfunction "1_1") (pintype "passive"))
      (node (ref "RN1") (pin "5") (pinfunction "5_5") (pintype "passive"))
    )
    (net (code "58") (name "Net-(LED6-Pad1)") (class "Default")
      (node (ref "LED6") (pin "1") (pinfunction "1_1") (pintype "passive"))
      (node (ref "RN1") (pin "6") (pinfunction "6_6") (pintype "passive"))
    )
    (net (code "59") (name "Net-(LED7-Pad1)") (class "Default")
      (node (ref "LED7") (pin "1") (pinfunction "1_1") (pintype "passive"))
      (node (ref "RN1") (pin "7") (pinfunction "7_7") (pintype "passive"))
    )
    (net (code "60") (name "unconnected-(*1-Pad2)") (class "Default")
      (node (ref "*1") (pin "2") (pinfunction "2_2") (pintype "passive"))
    )
    (net (code "61") (name "unconnected-(C5-Pad1)") (class "Default")
      (node (ref "C5") (pin "1") (pinfunction "1_1") (pintype "passive"))
    )
    (net (code "62") (name "unconnected-(C5-Pad5)") (class "Default")
      (node (ref "C5") (pin "5") (pinfunction "5_5") (pintype "passive"))
    )
    (net (code "63") (name "unconnected-(RN1-Pad8)") (class "Default")
      (node (ref "RN1") (pin "8") (pinfunction "8_8") (pintype "passive"))
    )
    (net (code "64") (name "unconnected-(RN1-Pad9)") (class "Default")
      (node (ref "RN1") (pin "9") (pinfunction "9_9") (pintype "passive"))
    )
  )
)
